# FOTA_MicroController_Status_LEDs.net
KiCad netlist of a schematic drawn in Altium Designer
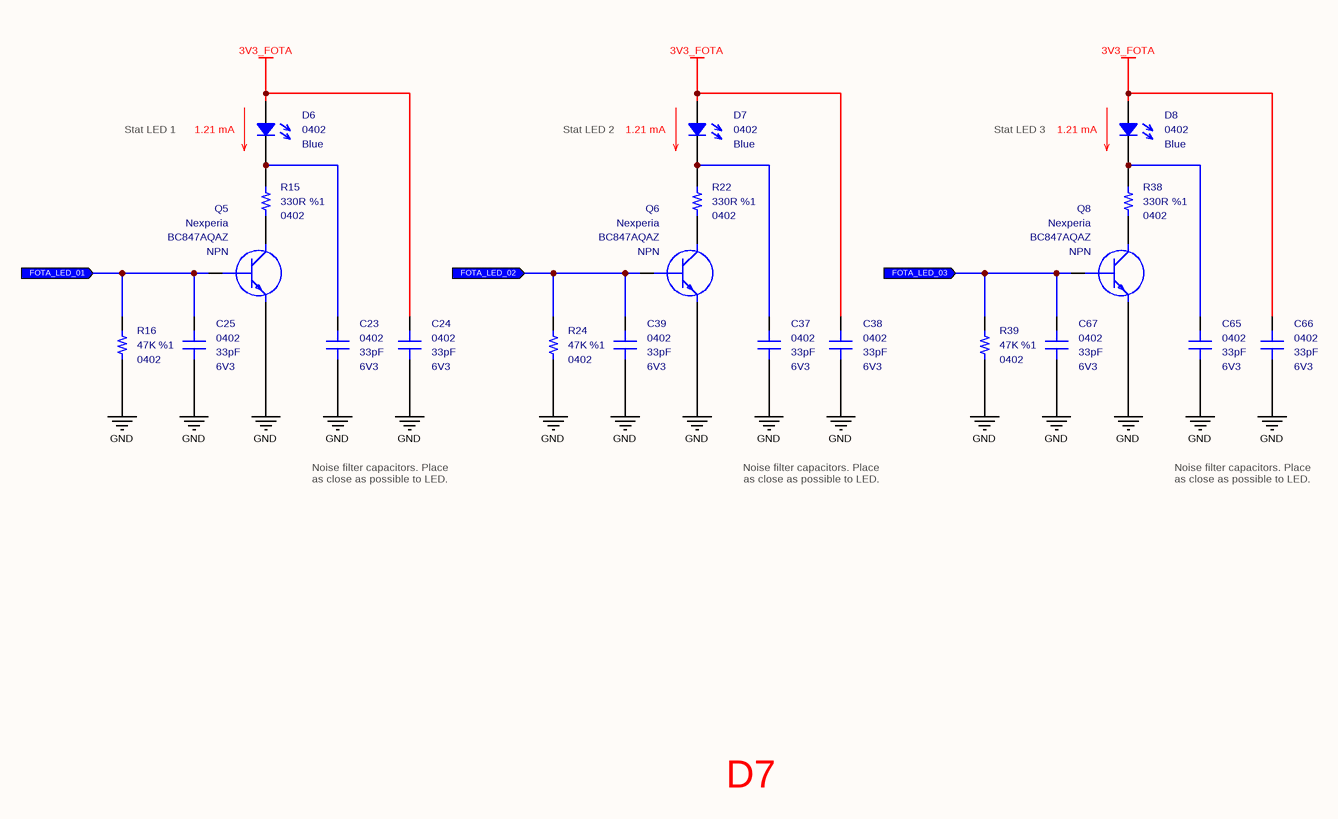
[diagram p0: FOTA MicroController Status LEDs.SchDoc]

(export (version "E")
  (design (tool "Eeschema 10.0.6"))
  (components
    (comp (ref "C23")
      (value "33pF")
      (footprint "CAPACITOR_0402")
      (description "Capacitor - 33pF [0402] (Ceramic)")
      (fields
        (field (name "MANUFACTURER_PART_NUMBER") "C0402C330J9RACAUTO")
        (field (name "MOUSER_PART_NUMBER") "80-C0402C330J9RAUTO")
        (field (name "CASE") "0402")
        (field (name "VOLTAGE") "6V3")
      )
      (libsource (lib "Ovoo_Schematic") (part "Capacitor - 33pF [0402-6V3]"))
    )
    (comp (ref "C24")
      (value "33pF")
      (footprint "CAPACITOR_0402")
      (description "Capacitor - 33pF [0402] (Ceramic)")
      (fields
        (field (name "MANUFACTURER_PART_NUMBER") "C0402C330J9RACAUTO")
        (field (name "MOUSER_PART_NUMBER") "80-C0402C330J9RAUTO")
        (field (name "CASE") "0402")
        (field (name "VOLTAGE") "6V3")
      )
      (libsource (lib "Ovoo_Schematic") (part "Capacitor - 33pF [0402-6V3]"))
    )
    (comp (ref "C25")
      (value "33pF")
      (footprint "CAPACITOR_0402")
      (description "Capacitor - 33pF [0402] (Ceramic)")
      (fields
        (field (name "MANUFACTURER_PART_NUMBER") "C0402C330J9RACAUTO")
        (field (name "MOUSER_PART_NUMBER") "80-C0402C330J9RAUTO")
        (field (name "CASE") "0402")
        (field (name "VOLTAGE") "6V3")
      )
      (libsource (lib "Ovoo_Schematic") (part "Capacitor - 33pF [0402-6V3]"))
    )
    (comp (ref "C37")
      (value "33pF")
      (footprint "CAPACITOR_0402")
      (description "Capacitor - 33pF [0402] (Ceramic)")
      (fields
        (field (name "MANUFACTURER_PART_NUMBER") "C0402C330J9RACAUTO")
        (field (name "MOUSER_PART_NUMBER") "80-C0402C330J9RAUTO")
        (field (name "CASE") "0402")
        (field (name "VOLTAGE") "6V3")
      )
      (libsource (lib "Ovoo_Schematic") (part "Capacitor - 33pF [0402-6V3]"))
    )
    (comp (ref "C38")
      (value "33pF")
      (footprint "CAPACITOR_0402")
      (description "Capacitor - 33pF [0402] (Ceramic)")
      (fields
        (field (name "MANUFACTURER_PART_NUMBER") "C0402C330J9RACAUTO")
        (field (name "MOUSER_PART_NUMBER") "80-C0402C330J9RAUTO")
        (field (name "CASE") "0402")
        (field (name "VOLTAGE") "6V3")
      )
      (libsource (lib "Ovoo_Schematic") (part "Capacitor - 33pF [0402-6V3]"))
    )
    (comp (ref "C39")
      (value "33pF")
      (footprint "CAPACITOR_0402")
      (description "Capacitor - 33pF [0402] (Ceramic)")
      (fields
        (field (name "MANUFACTURER_PART_NUMBER") "C0402C330J9RACAUTO")
        (field (name "MOUSER_PART_NUMBER") "80-C0402C330J9RAUTO")
        (field (name "CASE") "0402")
        (field (name "VOLTAGE") "6V3")
      )
      (libsource (lib "Ovoo_Schematic") (part "Capacitor - 33pF [0402-6V3]"))
    )
    (comp (ref "C65")
      (value "33pF")
      (footprint "CAPACITOR_0402")
      (description "Capacitor - 33pF [0402] (Ceramic)")
      (fields
        (field (name "MANUFACTURER_PART_NUMBER") "C0402C330J9RACAUTO")
        (field (name "MOUSER_PART_NUMBER") "80-C0402C330J9RAUTO")
        (field (name "CASE") "0402")
        (field (name "VOLTAGE") "6V3")
      )
      (libsource (lib "Ovoo_Schematic") (part "Capacitor - 33pF [0402-6V3]"))
    )
    (comp (ref "C66")
      (value "33pF")
      (footprint "CAPACITOR_0402")
      (description "Capacitor - 33pF [0402] (Ceramic)")
      (fields
        (field (name "MANUFACTURER_PART_NUMBER") "C0402C330J9RACAUTO")
        (field (name "MOUSER_PART_NUMBER") "80-C0402C330J9RAUTO")
        (field (name "CASE") "0402")
        (field (name "VOLTAGE") "6V3")
      )
      (libsource (lib "Ovoo_Schematic") (part "Capacitor - 33pF [0402-6V3]"))
    )
    (comp (ref "C67")
      (value "33pF")
      (footprint "CAPACITOR_0402")
      (description "Capacitor - 33pF [0402] (Ceramic)")
      (fields
        (field (name "MANUFACTURER_PART_NUMBER") "C0402C330J9RACAUTO")
        (field (name "MOUSER_PART_NUMBER") "80-C0402C330J9RAUTO")
        (field (name "CASE") "0402")
        (field (name "VOLTAGE") "6V3")
      )
      (libsource (lib "Ovoo_Schematic") (part "Capacitor - 33pF [0402-6V3]"))
    )
    (comp (ref "D6")
      (value "SMD LED (Blue)")
      (footprint "LED_0402")
      (description "Standard LEDs - SMD PICOLEDTM;BLUE LED; 25M @ 5MA")
      (fields
        (field (name "MANUFACTURER_PART_NUMBER") "SMLP13BC8TT86")
        (field (name "MOUSER_PART_NUMBER") "755-SMLP13BC8TT86")
        (field (name "CASE") "0402")
        (field (name "COLOR") "Blue")
      )
      (libsource (lib "Ovoo_Schematic") (part "Diode - LED (0402-Blue)"))
    )
    (comp (ref "D7")
      (value "SMD LED (Blue)")
      (footprint "LED_0402")
      (description "Standard LEDs - SMD PICOLEDTM;BLUE LED; 25M @ 5MA")
      (fields
        (field (name "MANUFACTURER_PART_NUMBER") "SMLP13BC8TT86")
        (field (name "MOUSER_PART_NUMBER") "755-SMLP13BC8TT86")
        (field (name "CASE") "0402")
        (field (name "COLOR") "Blue")
      )
      (libsource (lib "Ovoo_Schematic") (part "Diode - LED (0402-Blue)"))
    )
    (comp (ref "D8")
      (value "SMD LED (Blue)")
      (footprint "LED_0402")
      (description "Standard LEDs - SMD PICOLEDTM;BLUE LED; 25M @ 5MA")
      (fields
        (field (name "MANUFACTURER_PART_NUMBER") "SMLP13BC8TT86")
        (field (name "MOUSER_PART_NUMBER") "755-SMLP13BC8TT86")
        (field (name "CASE") "0402")
        (field (name "COLOR") "Blue")
      )
      (libsource (lib "Ovoo_Schematic") (part "Diode - LED (0402-Blue)"))
    )
    (comp (ref "Q5")
      (value "Bipolar NPN Transistors")
      (footprint "SOT1215")
      (description "Bipolar Transistors - BJT BC847AQA/DFN1010D-3/REEL 7\" Q2")
      (fields
        (field (name "MOUSER_PART_NUMBER") "771-BC847AQAZ")
        (field (name "MANUFACTURER_NAME") "Nexperia")
        (field (name "MANUFACTURER_PART_NUMBER") "BC847AQAZ")
        (field (name "POLARITY") "NPN")
      )
      (libsource (lib "Ovoo_Schematic") (part "Transistor - BC847"))
    )
    (comp (ref "Q6")
      (value "Bipolar NPN Transistors")
      (footprint "SOT1215")
      (description "Bipolar Transistors - BJT BC847AQA/DFN1010D-3/REEL 7\" Q2")
      (fields
        (field (name "MOUSER_PART_NUMBER") "771-BC847AQAZ")
        (field (name "MANUFACTURER_NAME") "Nexperia")
        (field (name "MANUFACTURER_PART_NUMBER") "BC847AQAZ")
        (field (name "POLARITY") "NPN")
      )
      (libsource (lib "Ovoo_Schematic") (part "Transistor - BC847"))
    )
    (comp (ref "Q8")
      (value "Bipolar NPN Transistors")
      (footprint "SOT1215")
      (description "Bipolar Transistors - BJT BC847AQA/DFN1010D-3/REEL 7\" Q2")
      (fields
        (field (name "MOUSER_PART_NUMBER") "771-BC847AQAZ")
        (field (name "MANUFACTURER_NAME") "Nexperia")
        (field (name "MANUFACTURER_PART_NUMBER") "BC847AQAZ")
        (field (name "POLARITY") "NPN")
      )
      (libsource (lib "Ovoo_Schematic") (part "Transistor - BC847"))
    )
    (comp (ref "R15")
      (value "330R")
      (footprint "RESISTOR_0402")
      (description "Thick Film Resistors - SMD 1/16 W 330 Ohm 1%")
      (fields
        (field (name "MANUFACTURER_PART_NUMBER") "CRCW0402330RFKED")
        (field (name "MOUSER_PART_NUMBER") "71-CRCW0402-330-E3")
        (field (name "TOLERANCE") "%1")
        (field (name "CASE") "0402")
      )
      (libsource (lib "Ovoo_Schematic") (part "Resistor - 330R"))
    )
    (comp (ref "R16")
      (value "47K")
      (footprint "RESISTOR_0402")
      (description "Thick Film Resistors - SMD 1/16 W 47 Kohms 1%")
      (fields
        (field (name "MANUFACTURER_PART_NUMBER") "CRCW040247K0FKED")
        (field (name "MOUSER_PART_NUMBER") "71-CRCW0402-47K-E3")
        (field (name "TOLERANCE") "%1")
        (field (name "CASE") "0402")
      )
      (libsource (lib "Ovoo_Schematic") (part "Resistor - 47K"))
    )
    (comp (ref "R22")
      (value "330R")
      (footprint "RESISTOR_0402")
      (description "Thick Film Resistors - SMD 1/16 W 330 Ohm 1%")
      (fields
        (field (name "MANUFACTURER_PART_NUMBER") "CRCW0402330RFKED")
        (field (name "MOUSER_PART_NUMBER") "71-CRCW0402-330-E3")
        (field (name "TOLERANCE") "%1")
        (field (name "CASE") "0402")
      )
      (libsource (lib "Ovoo_Schematic") (part "Resistor - 330R"))
    )
    (comp (ref "R24")
      (value "47K")
      (footprint "RESISTOR_0402")
      (description "Thick Film Resistors - SMD 1/16 W 47 Kohms 1%")
      (fields
        (field (name "MANUFACTURER_PART_NUMBER") "CRCW040247K0FKED")
        (field (name "MOUSER_PART_NUMBER") "71-CRCW0402-47K-E3")
        (field (name "TOLERANCE") "%1")
        (field (name "CASE") "0402")
      )
      (libsource (lib "Ovoo_Schematic") (part "Resistor - 47K"))
    )
    (comp (ref "R38")
      (value "330R")
      (footprint "RESISTOR_0402")
      (description "Thick Film Resistors - SMD 1/16 W 330 Ohm 1%")
      (fields
        (field (name "MANUFACTURER_PART_NUMBER") "CRCW0402330RFKED")
        (field (name "MOUSER_PART_NUMBER") "71-CRCW0402-330-E3")
        (field (name "TOLERANCE") "%1")
        (field (name "CASE") "0402")
      )
      (libsource (lib "Ovoo_Schematic") (part "Resistor - 330R"))
    )
    (comp (ref "R39")
      (value "47K")
      (footprint "RESISTOR_0402")
      (description "Thick Film Resistors - SMD 1/16 W 47 Kohms 1%")
      (fields
        (field (name "MANUFACTURER_PART_NUMBER") "CRCW040247K0FKED")
        (field (name "MOUSER_PART_NUMBER") "71-CRCW0402-47K-E3")
        (field (name "TOLERANCE") "%1")
        (field (name "CASE") "0402")
      )
      (libsource (lib "Ovoo_Schematic") (part "Resistor - 47K"))
    )
  )
  (nets
    (net (code "1") (name "/FOTA_LED_01") (class "Default")
      (node (ref "C25") (pin "1") (pinfunction "1_1") (pintype "passive"))
      (node (ref "Q5") (pin "1") (pinfunction "B_1") (pintype "passive"))
      (node (ref "R16") (pin "2") (pinfunction "2_2") (pintype "passive"))
    )
    (net (code "2") (name "/FOTA_LED_02") (class "Default")
      (node (ref "C39") (pin "1") (pinfunction "1_1") (pintype "passive"))
      (node (ref "Q6") (pin "1") (pinfunction "B_1") (pintype "passive"))
      (node (ref "R24") (pin "2") (pinfunction "2_2") (pintype "passive"))
    )
    (net (code "3") (name "/FOTA_LED_03") (class "Default")
      (node (ref "C67") (pin "1") (pinfunction "1_1") (pintype "passive"))
      (node (ref "Q8") (pin "1") (pinfunction "B_1") (pintype "passive"))
      (node (ref "R39") (pin "2") (pinfunction "2_2") (pintype "passive"))
    )
    (net (code "4") (name "3V3_FOTA") (class "Default")
      (node (ref "C24") (pin "1") (pinfunction "1_1") (pintype "passive"))
      (node (ref "C38") (pin "1") (pinfunction "1_1") (pintype "passive"))
      (node (ref "C66") (pin "1") (pinfunction "1_1") (pintype "passive"))
      (node (ref "D6") (pin "2") (pinfunction "2_2") (pintype "passive"))
      (node (ref "D7") (pin "2") (pinfunction "2_2") (pintype "passive"))
      (node (ref "D8") (pin "2") (pinfunction "2_2") (pintype "passive"))
    )
    (net (code "5") (name "GND") (class "Default")
      (node (ref "C23") (pin "2") (pinfunction "2_2") (pintype "passive"))
      (node (ref "C24") (pin "2") (pinfunction "2_2") (pintype "passive"))
      (node (ref "C25") (pin "2") (pinfunction "2_2") (pintype "passive"))
      (node (ref "C37") (pin "2") (pinfunction "2_2") (pintype "passive"))
      (node (ref "C38") (pin "2") (pinfunction "2_2") (pintype "passive"))
      (node (ref "C39") (pin "2") (pinfunction "2_2") (pintype "passive"))
      (node (ref "C65") (pin "2") (pinfunction "2_2") (pintype "passive"))
      (node (ref "C66") (pin "2") (pinfunction "2_2") (pintype "passive"))
      (node (ref "C67") (pin "2") (pinfunction "2_2") (pintype "passive"))
      (node (ref "Q5") (pin "2") (pinfunction "E_2") (pintype "passive"))
      (node (ref "Q6") (pin "2") (pinfunction "E_2") (pintype "passive"))
      (node (ref "Q8") (pin "2") (pinfunction "E_2") (pintype "passive"))
      (node (ref "R16") (pin "1") (pinfunction "1_1") (pintype "passive"))
      (node (ref "R24") (pin "1") (pinfunction "1_1") (pintype "passive"))
      (node (ref "R39") (pin "1") (pinfunction "1_1") (pintype "passive"))
    )
    (net (code "6") (name "Net-(C23-Pad1)") (class "Default")
      (node (ref "C23") (pin "1") (pinfunction "1_1") (pintype "passive"))
      (node (ref "D6") (pin "1") (pinfunction "1_1") (pintype "passive"))
      (node (ref "R15") (pin "2") (pinfunction "2_2") (pintype "passive"))
    )
    (net (code "7") (name "Net-(C37-Pad1)") (class "Default")
      (node (ref "C37") (pin "1") (pinfunction "1_1") (pintype "passive"))
      (node (ref "D7") (pin "1") (pinfunction "1_1") (pintype "passive"))
      (node (ref "R22") (pin "2") (pinfunction "2_2") (pintype "passive"))
    )
    (net (code "8") (name "Net-(C65-Pad1)") (class "Default")
      (node (ref "C65") (pin "1") (pinfunction "1_1") (pintype "passive"))
      (node (ref "D8") (pin "1") (pinfunction "1_1") (pintype "passive"))
      (node (ref "R38") (pin "2") (pinfunction "2_2") (pintype "passive"))
    )
    (net (code "9") (name "Net-(Q5-C)") (class "Default")
      (node (ref "Q5") (pin "3") (pinfunction "C_3") (pintype "passive"))
      (node (ref "R15") (pin "1") (pinfunction "1_1") (pintype "passive"))
    )
    (net (code "10") (name "Net-(Q6-C)") (class "Default")
      (node (ref "Q6") (pin "3") (pinfunction "C_3") (pintype "passive"))
      (node (ref "R22") (pin "1") (pinfunction "1_1") (pintype "passive"))
    )
    (net (code "11") (name "Net-(Q8-C)") (class "Default")
      (node (ref "Q8") (pin "3") (pinfunction "C_3") (pintype "passive"))
      (node (ref "R38") (pin "1") (pinfunction "1_1") (pintype "passive"))
    )
  )
)
